# DEBOUNCING.net
KiCad netlist of a schematic drawn in EAGLE
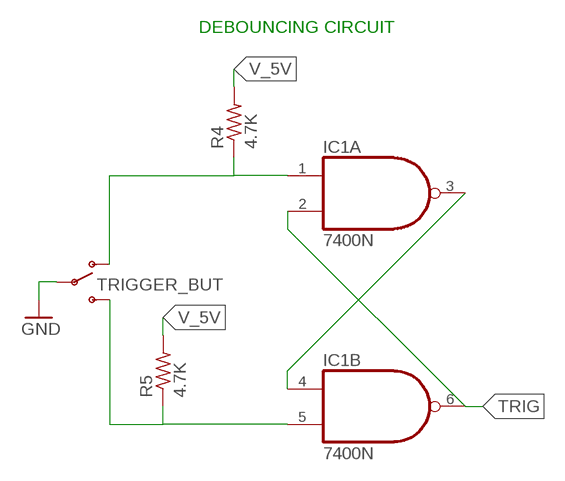
[diagram p0: schematic, sheet 1]

(export (version "E")
  (design (tool "Eeschema 10.0.6"))
  (components
    (comp (ref "IC1")
      (value "7400N")
      (footprint "eagle-import:DIL14")
      (libsource (lib "eagle-import") (part "7400N"))
    )
    (comp (ref "R4")
      (value "4.7K")
      (footprint "eagle-import:0207_2V")
      (libsource (lib "eagle-import") (part "R-US_0207/2V"))
    )
    (comp (ref "R5")
      (value "4.7K")
      (footprint "eagle-import:0207_2V")
      (libsource (lib "eagle-import") (part "R-US_0207/2V"))
    )
    (comp (ref "TRIGGER_BUT")
      (value "SWITCH-SPDTPTH")
      (footprint "eagle-import:SWITCH-SPDT")
      (libsource (lib "eagle-import") (part "SWITCH-SPDTPTH"))
    )
  )
  (nets
    (net (code "1") (name "GND") (class "Default")
      (node (ref "TRIGGER_BUT") (pin "2") (pinfunction "P_2") (pintype "passive"))
    )
    (net (code "2") (name "Net-(IC1A-I0)") (class "Default")
      (node (ref "IC1") (pin "1") (pinfunction "I0_1") (pintype "input"))
      (node (ref "R4") (pin "1") (pinfunction "1_1") (pintype "passive"))
      (node (ref "TRIGGER_BUT") (pin "1") (pinfunction "O_1") (pintype "passive"))
    )
    (net (code "3") (name "Net-(IC1A-O)") (class "Default")
      (node (ref "IC1") (pin "3") (pinfunction "O_3") (pintype "output"))
      (node (ref "IC1") (pin "4") (pinfunction "I0_4") (pintype "input"))
    )
    (net (code "4") (name "Net-(IC1B-I1)") (class "Default")
      (node (ref "IC1") (pin "5") (pinfunction "I1_5") (pintype "input"))
      (node (ref "R5") (pin "1") (pinfunction "1_1") (pintype "passive"))
      (node (ref "TRIGGER_BUT") (pin "3") (pinfunction "S_3") (pintype "passive"))
    )
    (net (code "5") (name "TRIG") (class "Default")
      (node (ref "IC1") (pin "2") (pinfunction "I1_2") (pintype "input"))
      (node (ref "IC1") (pin "6") (pinfunction "O_6") (pintype "output"))
    )
    (net (code "6") (name "V_5V") (class "Default")
      (node (ref "R4") (pin "2") (pinfunction "2_2") (pintype "passive"))
      (node (ref "R5") (pin "2") (pinfunction "2_2") (pintype "passive"))
    )
  )
)
